# Sensor_Board_2_04_HX711_DS18b2.net
KiCad netlist of a schematic drawn in EAGLE
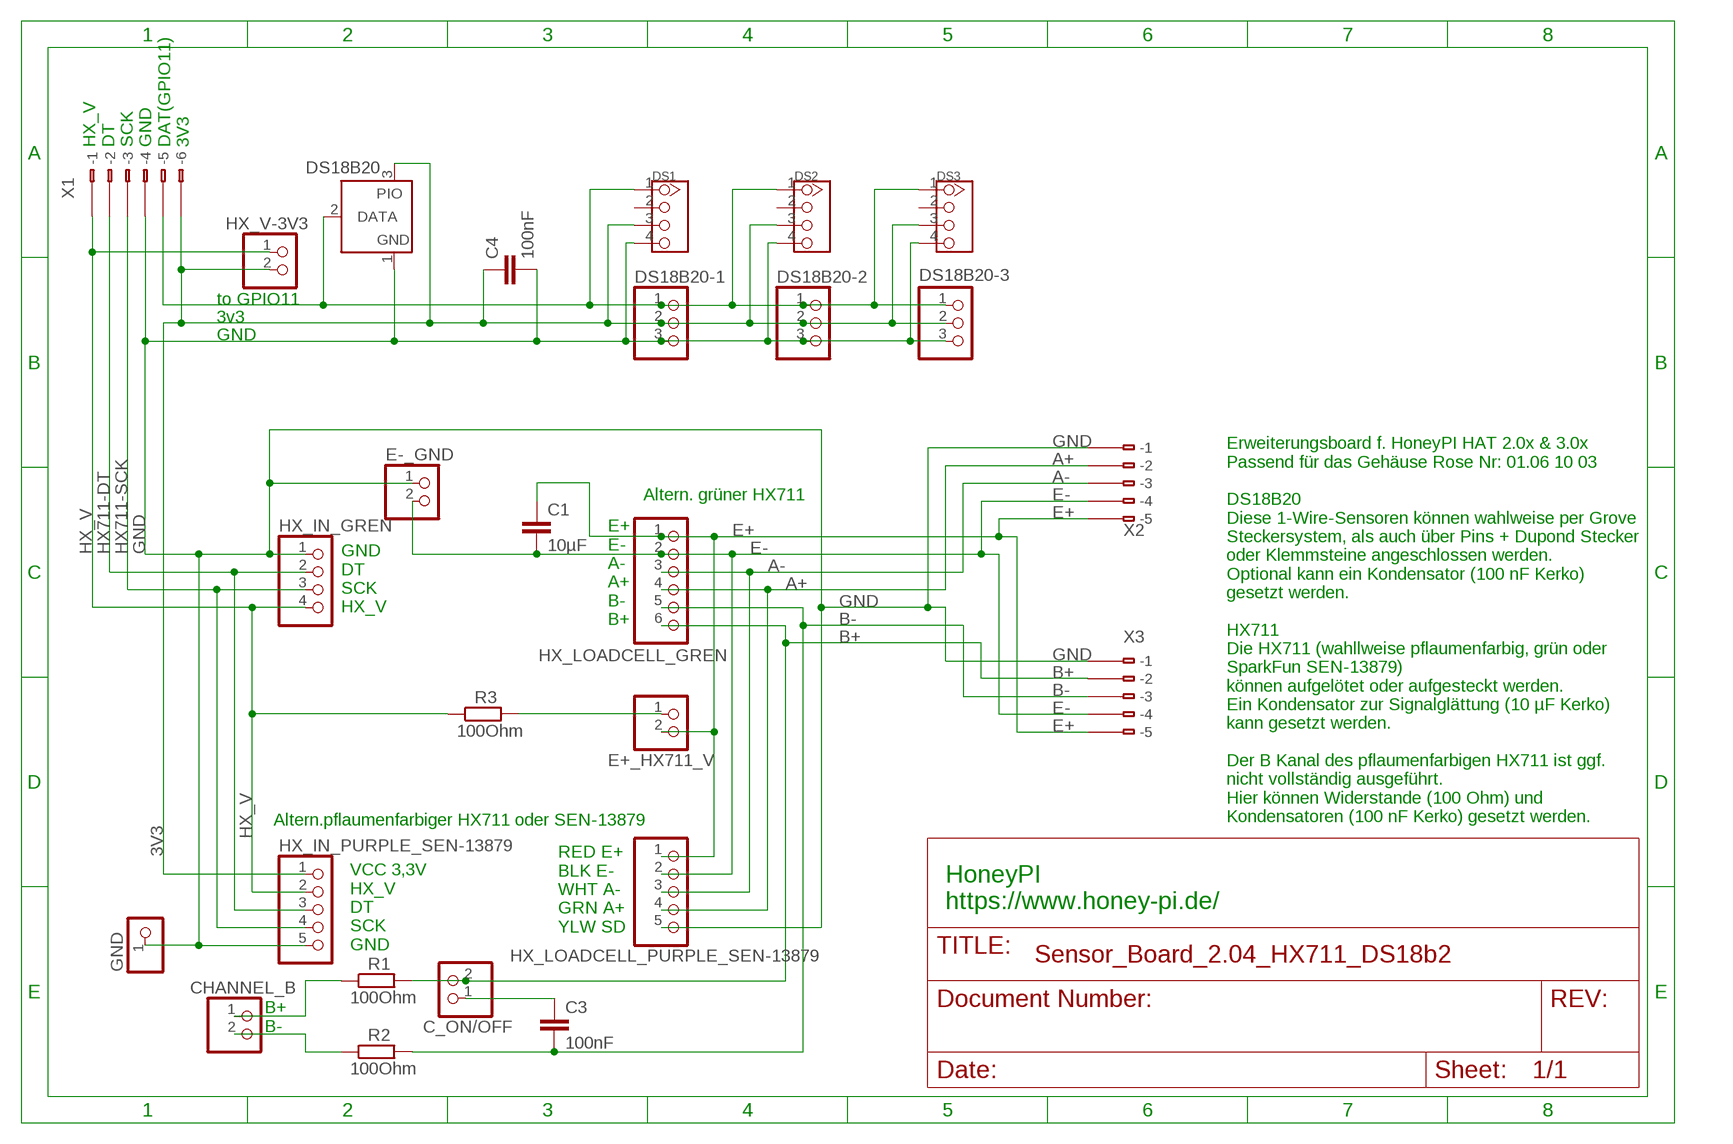
[diagram p0: schematic, sheet 1]

(export (version "E")
  (design (tool "Eeschema 10.0.6"))
  (components
    (comp (ref "C1")
      (value "10µF")
      (footprint "eagle-import:C5B2.5")
      (libsource (lib "eagle-import") (part "C5/2.5"))
    )
    (comp (ref "C3")
      (value "100nF")
      (footprint "eagle-import:C5B2.5")
      (libsource (lib "eagle-import") (part "C5/2.5"))
    )
    (comp (ref "C4")
      (value "100nF")
      (footprint "eagle-import:C5B2.5")
      (libsource (lib "eagle-import") (part "C5/2.5"))
    )
    (comp (ref "CHANNEL_B")
      (value "PINHD-1X2")
      (footprint "eagle-import:1X02")
      (libsource (lib "eagle-import") (part "PINHD-1X2"))
    )
    (comp (ref "C_ON/OFF")
      (value "PINHD-1X2")
      (footprint "eagle-import:1X02")
      (libsource (lib "eagle-import") (part "PINHD-1X2"))
    )
    (comp (ref "DS1")
      (value "TWIG-4P-2.0-2.0")
      (footprint "eagle-import:4P-2.0")
      (libsource (lib "eagle-import") (part "TWIG-4P-2.0-2.0"))
    )
    (comp (ref "DS2")
      (value "TWIG-4P-2.0-2.0")
      (footprint "eagle-import:4P-2.0")
      (libsource (lib "eagle-import") (part "TWIG-4P-2.0-2.0"))
    )
    (comp (ref "DS3")
      (value "TWIG-4P-2.0-2.0")
      (footprint "eagle-import:4P-2.0")
      (libsource (lib "eagle-import") (part "TWIG-4P-2.0-2.0"))
    )
    (comp (ref "DS18B20")
      (value "DS2405")
      (footprint "eagle-import:TO92-")
      (fields (field (name "MF") "DALLAS SEMICONDUCTOR"))
      (libsource (lib "eagle-import") (part "DS2405"))
    )
    (comp (ref "DS18B20-1")
      (value "PINHD-1X3")
      (footprint "eagle-import:1X03")
      (libsource (lib "eagle-import") (part "PINHD-1X3"))
    )
    (comp (ref "DS18B20-2")
      (value "PINHD-1X3")
      (footprint "eagle-import:1X03")
      (libsource (lib "eagle-import") (part "PINHD-1X3"))
    )
    (comp (ref "DS18B20-3")
      (value "PINHD-1X3")
      (footprint "eagle-import:1X03")
      (libsource (lib "eagle-import") (part "PINHD-1X3"))
    )
    (comp (ref "E+_HX711_V")
      (value "PINHD-1X2")
      (footprint "eagle-import:1X02")
      (libsource (lib "eagle-import") (part "PINHD-1X2"))
    )
    (comp (ref "E-_GND")
      (value "PINHD-1X2")
      (footprint "eagle-import:1X02")
      (libsource (lib "eagle-import") (part "PINHD-1X2"))
    )
    (comp (ref "GND")
      (value "PINHD-1X1")
      (footprint "eagle-import:1X01")
      (libsource (lib "eagle-import") (part "PINHD-1X1"))
    )
    (comp (ref "HX_IN_GREN")
      (value "PINHD-1X4")
      (footprint "eagle-import:1X04")
      (libsource (lib "eagle-import") (part "PINHD-1X4"))
    )
    (comp (ref "HX_IN_PURPLE_SEN-13879")
      (value "PINHD-1X5")
      (footprint "eagle-import:1X05")
      (libsource (lib "eagle-import") (part "PINHD-1X5"))
    )
    (comp (ref "HX_LOADCELL_GREN")
      (value "PINHD-1X6")
      (footprint "eagle-import:1X06")
      (libsource (lib "eagle-import") (part "PINHD-1X6"))
    )
    (comp (ref "HX_LOADCELL_PURPLE_SEN-13879")
      (value "PINHD-1X5")
      (footprint "eagle-import:1X05")
      (libsource (lib "eagle-import") (part "PINHD-1X5"))
    )
    (comp (ref "HX_V-3V3")
      (value "PINHD-1X2")
      (footprint "eagle-import:1X02")
      (libsource (lib "eagle-import") (part "PINHD-1X2"))
    )
    (comp (ref "R1")
      (value "100Ohm")
      (footprint "eagle-import:0207_10")
      (libsource (lib "eagle-import") (part "R-EU_0207/10"))
    )
    (comp (ref "R2")
      (value "100Ohm")
      (footprint "eagle-import:0207_10")
      (libsource (lib "eagle-import") (part "R-EU_0207/10"))
    )
    (comp (ref "R3")
      (value "100Ohm")
      (footprint "eagle-import:0207_10")
      (libsource (lib "eagle-import") (part "R-EU_0207/10"))
    )
    (comp (ref "X1")
      (value "233-506")
      (footprint "eagle-import:233-506")
      (fields (field (name "MF") "Wago Corporation") (field (name "MPN") "0233-0506"))
      (libsource (lib "eagle-import") (part "233-506"))
    )
    (comp (ref "X2")
      (value "233-505")
      (footprint "eagle-import:233-505")
      (fields (field (name "MF") "Wago Corporation") (field (name "MPN") "0233-0505"))
      (libsource (lib "eagle-import") (part "233-505"))
    )
    (comp (ref "X3")
      (value "233-505")
      (footprint "eagle-import:233-505")
      (fields (field (name "MF") "Wago Corporation") (field (name "MPN") "0233-0505"))
      (libsource (lib "eagle-import") (part "233-505"))
    )
  )
  (nets
    (net (code "1") (name "/3V3") (class "Default")
      (node (ref "C4") (pin "1") (pinfunction "1_1") (pintype "passive"))
      (node (ref "DS1") (pin "3") (pinfunction "3_3") (pintype "bidirectional"))
      (node (ref "DS18B20") (pin "3") (pinfunction "PIO_3") (pintype "passive"))
      (node (ref "DS18B20-1") (pin "2") (pinfunction "2_2") (pintype "passive"))
      (node (ref "DS18B20-2") (pin "2") (pinfunction "2_2") (pintype "passive"))
      (node (ref "DS18B20-3") (pin "2") (pinfunction "2_2") (pintype "passive"))
      (node (ref "DS2") (pin "3") (pinfunction "3_3") (pintype "bidirectional"))
      (node (ref "DS3") (pin "3") (pinfunction "3_3") (pintype "bidirectional"))
      (node (ref "HX_IN_PURPLE_SEN-13879") (pin "1") (pinfunction "1_1") (pintype "passive"))
      (node (ref "HX_V-3V3") (pin "2") (pinfunction "2_2") (pintype "passive"))
      (node (ref "X1") (pin "B6") (pinfunction "B-6_B6") (pintype "passive"))
    )
    (net (code "2") (name "/A+") (class "Default")
      (node (ref "HX_LOADCELL_GREN") (pin "4") (pinfunction "4_4") (pintype "passive"))
      (node (ref "HX_LOADCELL_PURPLE_SEN-13879") (pin "4") (pinfunction "4_4") (pintype "passive"))
      (node (ref "X2") (pin "B2") (pinfunction "B-2_B2") (pintype "passive"))
    )
    (net (code "3") (name "/A-") (class "Default")
      (node (ref "HX_LOADCELL_GREN") (pin "3") (pinfunction "3_3") (pintype "passive"))
      (node (ref "HX_LOADCELL_PURPLE_SEN-13879") (pin "3") (pinfunction "3_3") (pintype "passive"))
      (node (ref "X2") (pin "B3") (pinfunction "B-3_B3") (pintype "passive"))
    )
    (net (code "4") (name "/B+") (class "Default")
      (node (ref "C_ON/OFF") (pin "2") (pinfunction "2_2") (pintype "passive"))
      (node (ref "HX_LOADCELL_GREN") (pin "6") (pinfunction "6_6") (pintype "passive"))
      (node (ref "R1") (pin "2") (pinfunction "2_2") (pintype "passive"))
      (node (ref "X3") (pin "B2") (pinfunction "B-2_B2") (pintype "passive"))
    )
    (net (code "5") (name "/B-") (class "Default")
      (node (ref "C3") (pin "2") (pinfunction "2_2") (pintype "passive"))
      (node (ref "HX_LOADCELL_GREN") (pin "5") (pinfunction "5_5") (pintype "passive"))
      (node (ref "R2") (pin "2") (pinfunction "2_2") (pintype "passive"))
      (node (ref "X3") (pin "B3") (pinfunction "B-3_B3") (pintype "passive"))
    )
    (net (code "6") (name "/E+") (class "Default")
      (node (ref "C1") (pin "1") (pinfunction "1_1") (pintype "passive"))
      (node (ref "E+_HX711_V") (pin "2") (pinfunction "2_2") (pintype "passive"))
      (node (ref "HX_LOADCELL_GREN") (pin "1") (pinfunction "1_1") (pintype "passive"))
      (node (ref "HX_LOADCELL_PURPLE_SEN-13879") (pin "1") (pinfunction "1_1") (pintype "passive"))
      (node (ref "X2") (pin "B5") (pinfunction "B-5_B5") (pintype "passive"))
      (node (ref "X3") (pin "B5") (pinfunction "B-5_B5") (pintype "passive"))
    )
    (net (code "7") (name "/E-") (class "Default")
      (node (ref "C1") (pin "2") (pinfunction "2_2") (pintype "passive"))
      (node (ref "E-_GND") (pin "2") (pinfunction "2_2") (pintype "passive"))
      (node (ref "HX_LOADCELL_GREN") (pin "2") (pinfunction "2_2") (pintype "passive"))
      (node (ref "HX_LOADCELL_PURPLE_SEN-13879") (pin "2") (pinfunction "2_2") (pintype "passive"))
      (node (ref "X2") (pin "B4") (pinfunction "B-4_B4") (pintype "passive"))
      (node (ref "X3") (pin "B4") (pinfunction "B-4_B4") (pintype "passive"))
    )
    (net (code "8") (name "/GND") (class "Default")
      (node (ref "C4") (pin "2") (pinfunction "2_2") (pintype "passive"))
      (node (ref "DS1") (pin "4") (pinfunction "4_4") (pintype "bidirectional"))
      (node (ref "DS18B20") (pin "1") (pinfunction "GND_1") (pintype "passive"))
      (node (ref "DS18B20-1") (pin "3") (pinfunction "3_3") (pintype "passive"))
      (node (ref "DS18B20-2") (pin "3") (pinfunction "3_3") (pintype "passive"))
      (node (ref "DS18B20-3") (pin "3") (pinfunction "3_3") (pintype "passive"))
      (node (ref "DS2") (pin "4") (pinfunction "4_4") (pintype "bidirectional"))
      (node (ref "DS3") (pin "4") (pinfunction "4_4") (pintype "bidirectional"))
      (node (ref "E-_GND") (pin "1") (pinfunction "1_1") (pintype "passive"))
      (node (ref "GND") (pin "1") (pinfunction "1_1") (pintype "passive"))
      (node (ref "HX_IN_GREN") (pin "1") (pinfunction "1_1") (pintype "passive"))
      (node (ref "HX_IN_PURPLE_SEN-13879") (pin "5") (pinfunction "5_5") (pintype "passive"))
      (node (ref "HX_LOADCELL_PURPLE_SEN-13879") (pin "5") (pinfunction "5_5") (pintype "passive"))
      (node (ref "X1") (pin "B4") (pinfunction "B-4_B4") (pintype "passive"))
      (node (ref "X2") (pin "B1") (pinfunction "B-1_B1") (pintype "passive"))
      (node (ref "X3") (pin "B1") (pinfunction "B-1_B1") (pintype "passive"))
    )
    (net (code "9") (name "/HX711-DT") (class "Default")
      (node (ref "HX_IN_GREN") (pin "2") (pinfunction "2_2") (pintype "passive"))
      (node (ref "HX_IN_PURPLE_SEN-13879") (pin "3") (pinfunction "3_3") (pintype "passive"))
      (node (ref "X1") (pin "B2") (pinfunction "B-2_B2") (pintype "passive"))
    )
    (net (code "10") (name "/HX711-SCK") (class "Default")
      (node (ref "HX_IN_GREN") (pin "3") (pinfunction "3_3") (pintype "passive"))
      (node (ref "HX_IN_PURPLE_SEN-13879") (pin "4") (pinfunction "4_4") (pintype "passive"))
      (node (ref "X1") (pin "B3") (pinfunction "B-3_B3") (pintype "passive"))
    )
    (net (code "11") (name "/HX_V") (class "Default")
      (node (ref "HX_IN_GREN") (pin "4") (pinfunction "4_4") (pintype "passive"))
      (node (ref "HX_IN_PURPLE_SEN-13879") (pin "2") (pinfunction "2_2") (pintype "passive"))
      (node (ref "HX_V-3V3") (pin "1") (pinfunction "1_1") (pintype "passive"))
      (node (ref "R3") (pin "1") (pinfunction "1_1") (pintype "passive"))
      (node (ref "X1") (pin "B1") (pinfunction "B-1_B1") (pintype "passive"))
    )
    (net (code "12") (name "Net-(C3-Pad1)") (class "Default")
      (node (ref "C3") (pin "1") (pinfunction "1_1") (pintype "passive"))
      (node (ref "C_ON/OFF") (pin "1") (pinfunction "1_1") (pintype "passive"))
    )
    (net (code "13") (name "Net-(CHANNEL_B-Pad1)") (class "Default")
      (node (ref "CHANNEL_B") (pin "1") (pinfunction "1_1") (pintype "passive"))
      (node (ref "R1") (pin "1") (pinfunction "1_1") (pintype "passive"))
    )
    (net (code "14") (name "Net-(CHANNEL_B-Pad2)") (class "Default")
      (node (ref "CHANNEL_B") (pin "2") (pinfunction "2_2") (pintype "passive"))
      (node (ref "R2") (pin "1") (pinfunction "1_1") (pintype "passive"))
    )
    (net (code "15") (name "Net-(DS18B20-DATA)") (class "Default")
      (node (ref "DS1") (pin "1") (pinfunction "1_1") (pintype "bidirectional"))
      (node (ref "DS18B20") (pin "2") (pinfunction "DATA_2") (pintype "input"))
      (node (ref "DS18B20-1") (pin "1") (pinfunction "1_1") (pintype "passive"))
      (node (ref "DS18B20-2") (pin "1") (pinfunction "1_1") (pintype "passive"))
      (node (ref "DS18B20-3") (pin "1") (pinfunction "1_1") (pintype "passive"))
      (node (ref "DS2") (pin "1") (pinfunction "1_1") (pintype "bidirectional"))
      (node (ref "DS3") (pin "1") (pinfunction "1_1") (pintype "bidirectional"))
      (node (ref "X1") (pin "B5") (pinfunction "B-5_B5") (pintype "passive"))
    )
    (net (code "16") (name "Net-(E+_HX711_V-Pad1)") (class "Default")
      (node (ref "E+_HX711_V") (pin "1") (pinfunction "1_1") (pintype "passive"))
      (node (ref "R3") (pin "2") (pinfunction "2_2") (pintype "passive"))
    )
    (net (code "17") (name "unconnected-(DS1-Pad2)") (class "Default")
      (node (ref "DS1") (pin "2") (pinfunction "2_2") (pintype "bidirectional"))
    )
    (net (code "18") (name "unconnected-(DS2-Pad2)") (class "Default")
      (node (ref "DS2") (pin "2") (pinfunction "2_2") (pintype "bidirectional"))
    )
    (net (code "19") (name "unconnected-(DS3-Pad2)") (class "Default")
      (node (ref "DS3") (pin "2") (pinfunction "2_2") (pintype "bidirectional"))
    )
    (net (code "20") (name "unconnected-(X1--1-PadA1)") (class "Default")
      (node (ref "X1") (pin "A1") (pinfunction "-1_A1") (pintype "passive"))
    )
    (net (code "21") (name "unconnected-(X1--2-PadA2)") (class "Default")
      (node (ref "X1") (pin "A2") (pinfunction "-2_A2") (pintype "passive"))
    )
    (net (code "22") (name "unconnected-(X1--3-PadA3)") (class "Default")
      (node (ref "X1") (pin "A3") (pinfunction "-3_A3") (pintype "passive"))
    )
    (net (code "23") (name "unconnected-(X1--4-PadA4)") (class "Default")
      (node (ref "X1") (pin "A4") (pinfunction "-4_A4") (pintype "passive"))
    )
    (net (code "24") (name "unconnected-(X1--5-PadA5)") (class "Default")
      (node (ref "X1") (pin "A5") (pinfunction "-5_A5") (pintype "passive"))
    )
    (net (code "25") (name "unconnected-(X1--6-PadA6)") (class "Default")
      (node (ref "X1") (pin "A6") (pinfunction "-6_A6") (pintype "passive"))
    )
    (net (code "26") (name "unconnected-(X2--1-PadA1)") (class "Default")
      (node (ref "X2") (pin "A1") (pinfunction "-1_A1") (pintype "passive"))
    )
    (net (code "27") (name "unconnected-(X2--2-PadA2)") (class "Default")
      (node (ref "X2") (pin "A2") (pinfunction "-2_A2") (pintype "passive"))
    )
    (net (code "28") (name "unconnected-(X2--3-PadA3)") (class "Default")
      (node (ref "X2") (pin "A3") (pinfunction "-3_A3") (pintype "passive"))
    )
    (net (code "29") (name "unconnected-(X2--4-PadA4)") (class "Default")
      (node (ref "X2") (pin "A4") (pinfunction "-4_A4") (pintype "passive"))
    )
    (net (code "30") (name "unconnected-(X2--5-PadA5)") (class "Default")
      (node (ref "X2") (pin "A5") (pinfunction "-5_A5") (pintype "passive"))
    )
    (net (code "31") (name "unconnected-(X3--1-PadA1)") (class "Default")
      (node (ref "X3") (pin "A1") (pinfunction "-1_A1") (pintype "passive"))
    )
    (net (code "32") (name "unconnected-(X3--2-PadA2)") (class "Default")
      (node (ref "X3") (pin "A2") (pinfunction "-2_A2") (pintype "passive"))
    )
    (net (code "33") (name "unconnected-(X3--3-PadA3)") (class "Default")
      (node (ref "X3") (pin "A3") (pinfunction "-3_A3") (pintype "passive"))
    )
    (net (code "34") (name "unconnected-(X3--4-PadA4)") (class "Default")
      (node (ref "X3") (pin "A4") (pinfunction "-4_A4") (pintype "passive"))
    )
    (net (code "35") (name "unconnected-(X3--5-PadA5)") (class "Default")
      (node (ref "X3") (pin "A5") (pinfunction "-5_A5") (pintype "passive"))
    )
  )
)
